# Sensorino.net
KiCad netlist of a schematic drawn in EAGLE
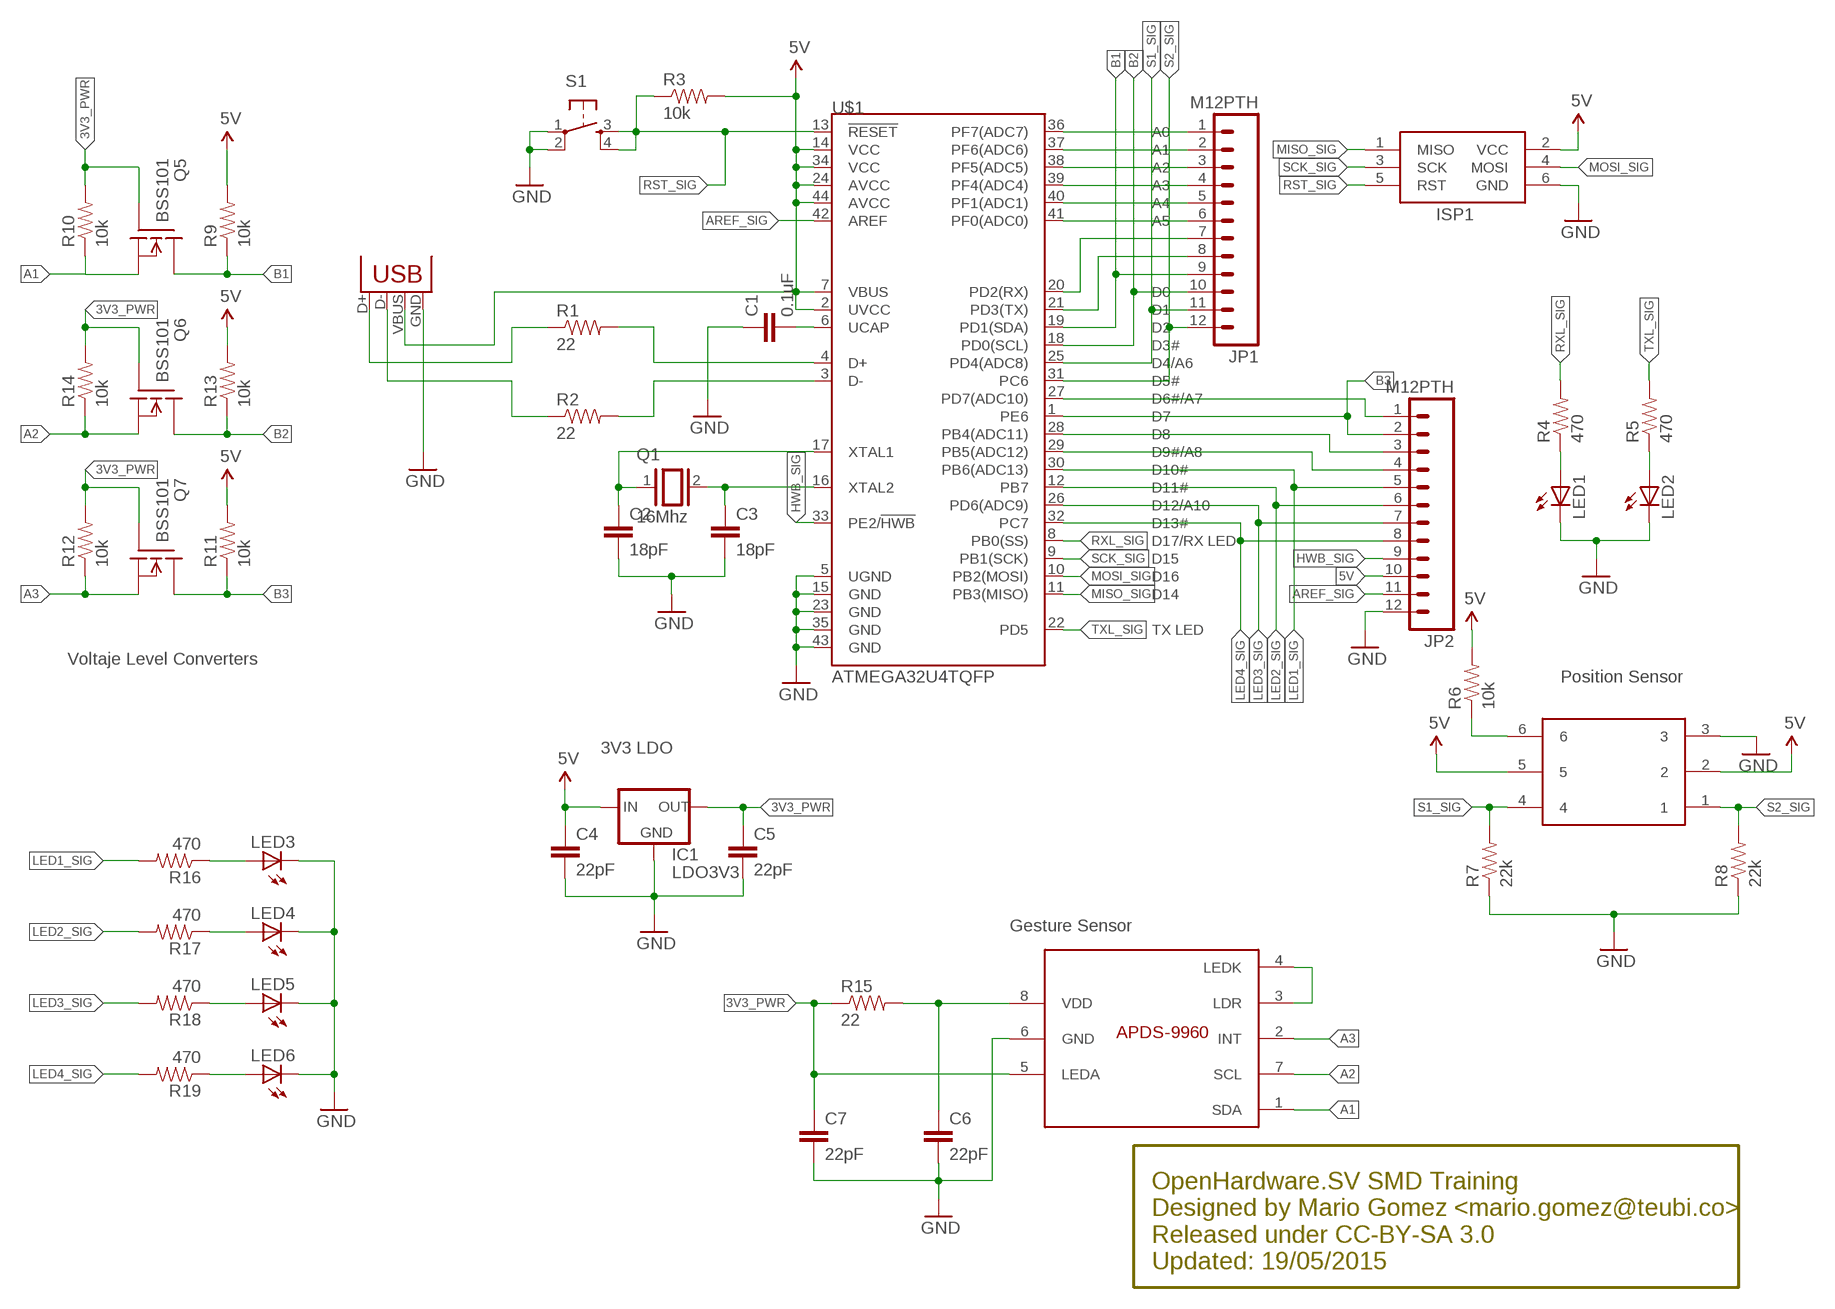
[diagram p0: schematic, sheet 1]

(export (version "E")
  (design (tool "Eeschema 10.0.6"))
  (components
    (comp (ref "C1")
      (value "0.1uF")
      (footprint "eagle-import:CAP-PTH-SMALL-KIT")
      (libsource (lib "eagle-import") (part "0.1UF-50V-20%(PTH)KIT-EZ"))
    )
    (comp (ref "C2")
      (value "18pF")
      (footprint "eagle-import:CAP-PTH-SMALL-KIT")
      (libsource (lib "eagle-import") (part "0.1UF-50V-20%(PTH)KIT-EZ"))
    )
    (comp (ref "C3")
      (value "18pF")
      (footprint "eagle-import:CAP-PTH-SMALL-KIT")
      (libsource (lib "eagle-import") (part "0.1UF-50V-20%(PTH)KIT-EZ"))
    )
    (comp (ref "C4")
      (value "22pF")
      (footprint "eagle-import:CAP-PTH-SMALL-KIT")
      (libsource (lib "eagle-import") (part "0.1UF-50V-20%(PTH)KIT-EZ"))
    )
    (comp (ref "C5")
      (value "22pF")
      (footprint "eagle-import:CAP-PTH-SMALL-KIT")
      (libsource (lib "eagle-import") (part "0.1UF-50V-20%(PTH)KIT-EZ"))
    )
    (comp (ref "C6")
      (value "22pF")
      (footprint "eagle-import:CAP-PTH-SMALL-KIT")
      (libsource (lib "eagle-import") (part "0.1UF-50V-20%(PTH)KIT-EZ"))
    )
    (comp (ref "C7")
      (value "22pF")
      (footprint "eagle-import:CAP-PTH-SMALL-KIT")
      (libsource (lib "eagle-import") (part "0.1UF-50V-20%(PTH)KIT-EZ"))
    )
    (comp (ref "IC1")
      (value "LDO3V3")
      (footprint "eagle-import:78XXL")
      (libsource (lib "eagle-import") (part "78XXL"))
    )
    (comp (ref "ISP1")
      (value "AVRISP-6")
      (footprint "eagle-import:AVRISP")
      (libsource (lib "eagle-import") (part "AVRISP-6"))
    )
    (comp (ref "JP1")
      (value "M12PTH")
      (footprint "eagle-import:1X12")
      (libsource (lib "eagle-import") (part "M12PTH"))
    )
    (comp (ref "JP2")
      (value "M12PTH")
      (footprint "eagle-import:1X12")
      (libsource (lib "eagle-import") (part "M12PTH"))
    )
    (comp (ref "LED1")
      (value "LED5MM")
      (footprint "eagle-import:LED5MM")
      (libsource (lib "eagle-import") (part "LED5MM"))
    )
    (comp (ref "LED2")
      (value "LED5MM")
      (footprint "eagle-import:LED5MM")
      (libsource (lib "eagle-import") (part "LED5MM"))
    )
    (comp (ref "LED3")
      (value "LED5MM")
      (footprint "eagle-import:LED5MM")
      (libsource (lib "eagle-import") (part "LED5MM"))
    )
    (comp (ref "LED4")
      (value "LED5MM")
      (footprint "eagle-import:LED5MM")
      (libsource (lib "eagle-import") (part "LED5MM"))
    )
    (comp (ref "LED5")
      (value "LED5MM")
      (footprint "eagle-import:LED5MM")
      (libsource (lib "eagle-import") (part "LED5MM"))
    )
    (comp (ref "LED6")
      (value "LED5MM")
      (footprint "eagle-import:LED5MM")
      (libsource (lib "eagle-import") (part "LED5MM"))
    )
    (comp (ref "Q1")
      (value "16Mhz")
      (footprint "eagle-import:QS")
      (libsource (lib "eagle-import") (part "XTAL/S"))
    )
    (comp (ref "Q5")
      (value "BSS101")
      (footprint "eagle-import:TO92")
      (libsource (lib "eagle-import") (part "BSS101"))
    )
    (comp (ref "Q6")
      (value "BSS101")
      (footprint "eagle-import:TO92")
      (libsource (lib "eagle-import") (part "BSS101"))
    )
    (comp (ref "Q7")
      (value "BSS101")
      (footprint "eagle-import:TO92")
      (libsource (lib "eagle-import") (part "BSS101"))
    )
    (comp (ref "R1")
      (value "22")
      (footprint "eagle-import:AXIAL-0.3")
      (libsource (lib "eagle-import") (part "RESISTORAXIAL-0.3"))
    )
    (comp (ref "R2")
      (value "22")
      (footprint "eagle-import:AXIAL-0.3")
      (libsource (lib "eagle-import") (part "RESISTORAXIAL-0.3"))
    )
    (comp (ref "R3")
      (value "10k")
      (footprint "eagle-import:AXIAL-0.3")
      (libsource (lib "eagle-import") (part "RESISTORAXIAL-0.3"))
    )
    (comp (ref "R4")
      (value "470")
      (footprint "eagle-import:AXIAL-0.3")
      (libsource (lib "eagle-import") (part "RESISTORAXIAL-0.3"))
    )
    (comp (ref "R5")
      (value "470")
      (footprint "eagle-import:AXIAL-0.3")
      (libsource (lib "eagle-import") (part "RESISTORAXIAL-0.3"))
    )
    (comp (ref "R6")
      (value "10k")
      (footprint "eagle-import:AXIAL-0.3")
      (libsource (lib "eagle-import") (part "RESISTORAXIAL-0.3"))
    )
    (comp (ref "R7")
      (value "22k")
      (footprint "eagle-import:AXIAL-0.3")
      (libsource (lib "eagle-import") (part "RESISTORAXIAL-0.3"))
    )
    (comp (ref "R8")
      (value "22k")
      (footprint "eagle-import:AXIAL-0.3")
      (libsource (lib "eagle-import") (part "RESISTORAXIAL-0.3"))
    )
    (comp (ref "R9")
      (value "10k")
      (footprint "eagle-import:AXIAL-0.3")
      (libsource (lib "eagle-import") (part "RESISTORAXIAL-0.3"))
    )
    (comp (ref "R10")
      (value "10k")
      (footprint "eagle-import:AXIAL-0.3")
      (libsource (lib "eagle-import") (part "RESISTORAXIAL-0.3"))
    )
    (comp (ref "R11")
      (value "10k")
      (footprint "eagle-import:AXIAL-0.3")
      (libsource (lib "eagle-import") (part "RESISTORAXIAL-0.3"))
    )
    (comp (ref "R12")
      (value "10k")
      (footprint "eagle-import:AXIAL-0.3")
      (libsource (lib "eagle-import") (part "RESISTORAXIAL-0.3"))
    )
    (comp (ref "R13")
      (value "10k")
      (footprint "eagle-import:AXIAL-0.3")
      (libsource (lib "eagle-import") (part "RESISTORAXIAL-0.3"))
    )
    (comp (ref "R14")
      (value "10k")
      (footprint "eagle-import:AXIAL-0.3")
      (libsource (lib "eagle-import") (part "RESISTORAXIAL-0.3"))
    )
    (comp (ref "R15")
      (value "22")
      (footprint "eagle-import:AXIAL-0.3")
      (libsource (lib "eagle-import") (part "RESISTORAXIAL-0.3"))
    )
    (comp (ref "R16")
      (value "470")
      (footprint "eagle-import:AXIAL-0.3")
      (libsource (lib "eagle-import") (part "RESISTORAXIAL-0.3"))
    )
    (comp (ref "R17")
      (value "470")
      (footprint "eagle-import:AXIAL-0.3")
      (libsource (lib "eagle-import") (part "RESISTORAXIAL-0.3"))
    )
    (comp (ref "R18")
      (value "470")
      (footprint "eagle-import:AXIAL-0.3")
      (libsource (lib "eagle-import") (part "RESISTORAXIAL-0.3"))
    )
    (comp (ref "R19")
      (value "470")
      (footprint "eagle-import:AXIAL-0.3")
      (libsource (lib "eagle-import") (part "RESISTORAXIAL-0.3"))
    )
    (comp (ref "S1")
      (value "TAC_SWITCHPTH")
      (footprint "eagle-import:TACTILE-PTH")
      (libsource (lib "eagle-import") (part "TAC_SWITCHPTH"))
    )
    (comp (ref "U$1")
      (value "ATMEGA32U4TQFP")
      (footprint "eagle-import:SPARKFUN-DIGITALIC_TQFP44")
      (libsource (lib "eagle-import") (part "ATMEGA32U4TQFP"))
    )
    (comp (ref "U$2")
      (value "USBPTH")
      (footprint "eagle-import:USB-B-PTH")
      (libsource (lib "eagle-import") (part "USBPTH"))
    )
    (comp (ref "U$3")
      (value "RPI-1031")
      (footprint "eagle-import:RPI-1031")
      (libsource (lib "eagle-import") (part "RPI-1031"))
    )
    (comp (ref "U$4")
      (value "APDS-9960")
      (footprint "eagle-import:APDS-9960")
      (libsource (lib "eagle-import") (part "APDS-9960"))
    )
  )
  (nets
    (net (code "1") (name "3V3_PWR") (class "Default")
      (node (ref "C5") (pin "1") (pinfunction "1_1") (pintype "passive"))
      (node (ref "C7") (pin "1") (pinfunction "1_1") (pintype "passive"))
      (node (ref "IC1") (pin "OUT") (pinfunction "OUT_OUT") (pintype "passive"))
      (node (ref "Q5") (pin "2") (pinfunction "G_2") (pintype "passive"))
      (node (ref "Q6") (pin "2") (pinfunction "G_2") (pintype "passive"))
      (node (ref "Q7") (pin "2") (pinfunction "G_2") (pintype "passive"))
      (node (ref "R10") (pin "P$2") (pinfunction "2_P$2") (pintype "passive"))
      (node (ref "R12") (pin "P$2") (pinfunction "2_P$2") (pintype "passive"))
      (node (ref "R14") (pin "P$2") (pinfunction "2_P$2") (pintype "passive"))
      (node (ref "R15") (pin "P$1") (pinfunction "1_P$1") (pintype "passive"))
      (node (ref "U$4") (pin "5") (pinfunction "LEDA_5") (pintype "bidirectional"))
    )
    (net (code "2") (name "5V") (class "Default")
      (node (ref "C4") (pin "1") (pinfunction "1_1") (pintype "passive"))
      (node (ref "IC1") (pin "IN") (pinfunction "IN_IN") (pintype "input"))
      (node (ref "ISP1") (pin "2") (pinfunction "VCC_2") (pintype "power_in"))
      (node (ref "JP2") (pin "10") (pinfunction "10_10") (pintype "passive"))
      (node (ref "R11") (pin "P$2") (pinfunction "2_P$2") (pintype "passive"))
      (node (ref "R13") (pin "P$2") (pinfunction "2_P$2") (pintype "passive"))
      (node (ref "R3") (pin "P$2") (pinfunction "2_P$2") (pintype "passive"))
      (node (ref "R6") (pin "P$2") (pinfunction "2_P$2") (pintype "passive"))
      (node (ref "R9") (pin "P$2") (pinfunction "2_P$2") (pintype "passive"))
      (node (ref "U$1") (pin "14") (pinfunction "VCC_14") (pintype "bidirectional"))
      (node (ref "U$1") (pin "2") (pinfunction "UVCC_2") (pintype "bidirectional"))
      (node (ref "U$1") (pin "24") (pinfunction "AVCC_24") (pintype "bidirectional"))
      (node (ref "U$1") (pin "34") (pinfunction "VCC_34") (pintype "bidirectional"))
      (node (ref "U$1") (pin "44") (pinfunction "AVCC_44") (pintype "bidirectional"))
      (node (ref "U$1") (pin "7") (pinfunction "VBUS_7") (pintype "bidirectional"))
      (node (ref "U$2") (pin "VBUS") (pinfunction "VBUS_VBUS") (pintype "bidirectional"))
      (node (ref "U$3") (pin "2") (pinfunction "2_2") (pintype "bidirectional"))
      (node (ref "U$3") (pin "5") (pinfunction "5_5") (pintype "bidirectional"))
    )
    (net (code "3") (name "A1") (class "Default")
      (node (ref "Q5") (pin "1") (pinfunction "S_1") (pintype "passive"))
      (node (ref "R10") (pin "P$1") (pinfunction "1_P$1") (pintype "passive"))
      (node (ref "U$4") (pin "1") (pinfunction "SDA_1") (pintype "bidirectional"))
    )
    (net (code "4") (name "A2") (class "Default")
      (node (ref "Q6") (pin "1") (pinfunction "S_1") (pintype "passive"))
      (node (ref "R14") (pin "P$1") (pinfunction "1_P$1") (pintype "passive"))
      (node (ref "U$4") (pin "7") (pinfunction "SCL_7") (pintype "bidirectional"))
    )
    (net (code "5") (name "A3") (class "Default")
      (node (ref "Q7") (pin "1") (pinfunction "S_1") (pintype "passive"))
      (node (ref "R12") (pin "P$1") (pinfunction "1_P$1") (pintype "passive"))
      (node (ref "U$4") (pin "2") (pinfunction "INT_2") (pintype "bidirectional"))
    )
    (net (code "6") (name "AREF_SIG") (class "Default")
      (node (ref "JP2") (pin "11") (pinfunction "11_11") (pintype "passive"))
      (node (ref "U$1") (pin "42") (pinfunction "AREF_42") (pintype "bidirectional"))
    )
    (net (code "7") (name "B1") (class "Default")
      (node (ref "JP1") (pin "9") (pinfunction "9_9") (pintype "passive"))
      (node (ref "Q5") (pin "3") (pinfunction "D_3") (pintype "passive"))
      (node (ref "R9") (pin "P$1") (pinfunction "1_P$1") (pintype "passive"))
      (node (ref "U$1") (pin "19") (pinfunction "PD1(SDA)_19") (pintype "bidirectional"))
    )
    (net (code "8") (name "B2") (class "Default")
      (node (ref "JP1") (pin "10") (pinfunction "10_10") (pintype "passive"))
      (node (ref "Q6") (pin "3") (pinfunction "D_3") (pintype "passive"))
      (node (ref "R13") (pin "P$1") (pinfunction "1_P$1") (pintype "passive"))
      (node (ref "U$1") (pin "18") (pinfunction "PD0(SCL)_18") (pintype "bidirectional"))
    )
    (net (code "9") (name "B3") (class "Default")
      (node (ref "JP2") (pin "2") (pinfunction "2_2") (pintype "passive"))
      (node (ref "Q7") (pin "3") (pinfunction "D_3") (pintype "passive"))
      (node (ref "R11") (pin "P$1") (pinfunction "1_P$1") (pintype "passive"))
      (node (ref "U$1") (pin "1") (pinfunction "PE6_1") (pintype "bidirectional"))
    )
    (net (code "10") (name "GND") (class "Default")
      (node (ref "C1") (pin "1") (pinfunction "1_1") (pintype "passive"))
      (node (ref "C2") (pin "2") (pinfunction "2_2") (pintype "passive"))
      (node (ref "C3") (pin "2") (pinfunction "2_2") (pintype "passive"))
      (node (ref "C4") (pin "2") (pinfunction "2_2") (pintype "passive"))
      (node (ref "C5") (pin "2") (pinfunction "2_2") (pintype "passive"))
      (node (ref "C6") (pin "2") (pinfunction "2_2") (pintype "passive"))
      (node (ref "C7") (pin "2") (pinfunction "2_2") (pintype "passive"))
      (node (ref "IC1") (pin "GND") (pinfunction "GND_GND") (pintype "input"))
      (node (ref "ISP1") (pin "6") (pinfunction "GND_6") (pintype "power_in"))
      (node (ref "JP2") (pin "12") (pinfunction "12_12") (pintype "passive"))
      (node (ref "LED1") (pin "K") (pinfunction "C_K") (pintype "passive"))
      (node (ref "LED2") (pin "K") (pinfunction "C_K") (pintype "passive"))
      (node (ref "LED3") (pin "K") (pinfunction "C_K") (pintype "passive"))
      (node (ref "LED4") (pin "K") (pinfunction "C_K") (pintype "passive"))
      (node (ref "LED5") (pin "K") (pinfunction "C_K") (pintype "passive"))
      (node (ref "LED6") (pin "K") (pinfunction "C_K") (pintype "passive"))
      (node (ref "R7") (pin "P$1") (pinfunction "1_P$1") (pintype "passive"))
      (node (ref "R8") (pin "P$1") (pinfunction "1_P$1") (pintype "passive"))
      (node (ref "S1") (pin "1") (pinfunction "1_1") (pintype "passive"))
      (node (ref "S1") (pin "2") (pinfunction "2_2") (pintype "passive"))
      (node (ref "U$1") (pin "15") (pinfunction "GND_15") (pintype "bidirectional"))
      (node (ref "U$1") (pin "23") (pinfunction "GND_23") (pintype "bidirectional"))
      (node (ref "U$1") (pin "35") (pinfunction "GND_35") (pintype "bidirectional"))
      (node (ref "U$1") (pin "43") (pinfunction "GND_43") (pintype "bidirectional"))
      (node (ref "U$1") (pin "5") (pinfunction "UGND_5") (pintype "bidirectional"))
      (node (ref "U$2") (pin "GND") (pinfunction "GND_GND") (pintype "bidirectional"))
      (node (ref "U$3") (pin "3") (pinfunction "3_3") (pintype "bidirectional"))
      (node (ref "U$4") (pin "6") (pinfunction "GND_6") (pintype "bidirectional"))
    )
    (net (code "11") (name "HWB_SIG") (class "Default")
      (node (ref "JP2") (pin "9") (pinfunction "9_9") (pintype "passive"))
      (node (ref "U$1") (pin "33") (pinfunction "PE2/~{HWB}_33") (pintype "bidirectional"))
    )
    (net (code "12") (name "LED1_SIG") (class "Default")
      (node (ref "JP2") (pin "5") (pinfunction "5_5") (pintype "passive"))
      (node (ref "R16") (pin "P$2") (pinfunction "2_P$2") (pintype "passive"))
      (node (ref "U$1") (pin "30") (pinfunction "PB6(ADC13)_30") (pintype "bidirectional"))
    )
    (net (code "13") (name "LED2_SIG") (class "Default")
      (node (ref "JP2") (pin "6") (pinfunction "6_6") (pintype "passive"))
      (node (ref "R17") (pin "P$2") (pinfunction "2_P$2") (pintype "passive"))
      (node (ref "U$1") (pin "12") (pinfunction "PB7_12") (pintype "bidirectional"))
    )
    (net (code "14") (name "LED3_SIG") (class "Default")
      (node (ref "JP2") (pin "7") (pinfunction "7_7") (pintype "passive"))
      (node (ref "R18") (pin "P$2") (pinfunction "2_P$2") (pintype "passive"))
      (node (ref "U$1") (pin "26") (pinfunction "PD6(ADC9)_26") (pintype "bidirectional"))
    )
    (net (code "15") (name "LED4_SIG") (class "Default")
      (node (ref "JP2") (pin "8") (pinfunction "8_8") (pintype "passive"))
      (node (ref "R19") (pin "P$2") (pinfunction "2_P$2") (pintype "passive"))
      (node (ref "U$1") (pin "32") (pinfunction "PC7_32") (pintype "bidirectional"))
    )
    (net (code "16") (name "MISO_SIG") (class "Default")
      (node (ref "ISP1") (pin "1") (pinfunction "MISO_1") (pintype "input"))
      (node (ref "U$1") (pin "11") (pinfunction "PB3(MISO)_11") (pintype "bidirectional"))
    )
    (net (code "17") (name "MOSI_SIG") (class "Default")
      (node (ref "ISP1") (pin "4") (pinfunction "MOSI_4") (pintype "output"))
      (node (ref "U$1") (pin "10") (pinfunction "PB2(MOSI)_10") (pintype "bidirectional"))
    )
    (net (code "18") (name "Net-(R1-1)") (class "Default")
      (node (ref "R1") (pin "P$1") (pinfunction "1_P$1") (pintype "passive"))
      (node (ref "U$2") (pin "D+") (pinfunction "D+_D+") (pintype "bidirectional"))
    )
    (net (code "19") (name "Net-(R1-2)") (class "Default")
      (node (ref "R1") (pin "P$2") (pinfunction "2_P$2") (pintype "passive"))
      (node (ref "U$1") (pin "4") (pinfunction "D+_4") (pintype "bidirectional"))
    )
    (net (code "20") (name "Net-(R2-1)") (class "Default")
      (node (ref "R2") (pin "P$1") (pinfunction "1_P$1") (pintype "passive"))
      (node (ref "U$2") (pin "D-") (pinfunction "D-_D-") (pintype "bidirectional"))
    )
    (net (code "21") (name "Net-(R2-2)") (class "Default")
      (node (ref "R2") (pin "P$2") (pinfunction "2_P$2") (pintype "passive"))
      (node (ref "U$1") (pin "3") (pinfunction "D-_3") (pintype "bidirectional"))
    )
    (net (code "22") (name "Net-(R4-1)") (class "Default")
      (node (ref "LED1") (pin "A") (pinfunction "A_A") (pintype "passive"))
      (node (ref "R4") (pin "P$1") (pinfunction "1_P$1") (pintype "passive"))
    )
    (net (code "23") (name "Net-(R5-1)") (class "Default")
      (node (ref "LED2") (pin "A") (pinfunction "A_A") (pintype "passive"))
      (node (ref "R5") (pin "P$1") (pinfunction "1_P$1") (pintype "passive"))
    )
    (net (code "24") (name "Net-(R6-1)") (class "Default")
      (node (ref "R6") (pin "P$1") (pinfunction "1_P$1") (pintype "passive"))
      (node (ref "U$3") (pin "6") (pinfunction "6_6") (pintype "bidirectional"))
    )
    (net (code "25") (name "Net-(R15-2)") (class "Default")
      (node (ref "C6") (pin "1") (pinfunction "1_1") (pintype "passive"))
      (node (ref "R15") (pin "P$2") (pinfunction "2_P$2") (pintype "passive"))
      (node (ref "U$4") (pin "8") (pinfunction "VDD_8") (pintype "bidirectional"))
    )
    (net (code "26") (name "Net-(R16-1)") (class "Default")
      (node (ref "LED3") (pin "A") (pinfunction "A_A") (pintype "passive"))
      (node (ref "R16") (pin "P$1") (pinfunction "1_P$1") (pintype "passive"))
    )
    (net (code "27") (name "Net-(R17-1)") (class "Default")
      (node (ref "LED4") (pin "A") (pinfunction "A_A") (pintype "passive"))
      (node (ref "R17") (pin "P$1") (pinfunction "1_P$1") (pintype "passive"))
    )
    (net (code "28") (name "Net-(R18-1)") (class "Default")
      (node (ref "LED5") (pin "A") (pinfunction "A_A") (pintype "passive"))
      (node (ref "R18") (pin "P$1") (pinfunction "1_P$1") (pintype "passive"))
    )
    (net (code "29") (name "Net-(R19-1)") (class "Default")
      (node (ref "LED6") (pin "A") (pinfunction "A_A") (pintype "passive"))
      (node (ref "R19") (pin "P$1") (pinfunction "1_P$1") (pintype "passive"))
    )
    (net (code "30") (name "Net-(U$1-PB4(ADC11))") (class "Default")
      (node (ref "JP2") (pin "3") (pinfunction "3_3") (pintype "passive"))
      (node (ref "U$1") (pin "28") (pinfunction "PB4(ADC11)_28") (pintype "bidirectional"))
    )
    (net (code "31") (name "Net-(U$1-PB5(ADC12))") (class "Default")
      (node (ref "JP2") (pin "4") (pinfunction "4_4") (pintype "passive"))
      (node (ref "U$1") (pin "29") (pinfunction "PB5(ADC12)_29") (pintype "bidirectional"))
    )
    (net (code "32") (name "Net-(U$1-PD2(RX))") (class "Default")
      (node (ref "JP1") (pin "7") (pinfunction "7_7") (pintype "passive"))
      (node (ref "U$1") (pin "20") (pinfunction "PD2(RX)_20") (pintype "bidirectional"))
    )
    (net (code "33") (name "Net-(U$1-PD3(TX))") (class "Default")
      (node (ref "JP1") (pin "8") (pinfunction "8_8") (pintype "passive"))
      (node (ref "U$1") (pin "21") (pinfunction "PD3(TX)_21") (pintype "bidirectional"))
    )
    (net (code "34") (name "Net-(U$1-PD7(ADC10))") (class "Default")
      (node (ref "JP2") (pin "1") (pinfunction "1_1") (pintype "passive"))
      (node (ref "U$1") (pin "27") (pinfunction "PD7(ADC10)_27") (pintype "bidirectional"))
    )
    (net (code "35") (name "Net-(U$1-PF0(ADC0))") (class "Default")
      (node (ref "JP1") (pin "6") (pinfunction "6_6") (pintype "passive"))
      (node (ref "U$1") (pin "41") (pinfunction "PF0(ADC0)_41") (pintype "bidirectional"))
    )
    (net (code "36") (name "Net-(U$1-PF1(ADC1))") (class "Default")
      (node (ref "JP1") (pin "5") (pinfunction "5_5") (pintype "passive"))
      (node (ref "U$1") (pin "40") (pinfunction "PF1(ADC1)_40") (pintype "bidirectional"))
    )
    (net (code "37") (name "Net-(U$1-PF4(ADC4))") (class "Default")
      (node (ref "JP1") (pin "4") (pinfunction "4_4") (pintype "passive"))
      (node (ref "U$1") (pin "39") (pinfunction "PF4(ADC4)_39") (pintype "bidirectional"))
    )
    (net (code "38") (name "Net-(U$1-PF5(ADC5))") (class "Default")
      (node (ref "JP1") (pin "3") (pinfunction "3_3") (pintype "passive"))
      (node (ref "U$1") (pin "38") (pinfunction "PF5(ADC5)_38") (pintype "bidirectional"))
    )
    (net (code "39") (name "Net-(U$1-PF6(ADC6))") (class "Default")
      (node (ref "JP1") (pin "2") (pinfunction "2_2") (pintype "passive"))
      (node (ref "U$1") (pin "37") (pinfunction "PF6(ADC6)_37") (pintype "bidirectional"))
    )
    (net (code "40") (name "Net-(U$1-PF7(ADC7))") (class "Default")
      (node (ref "JP1") (pin "1") (pinfunction "1_1") (pintype "passive"))
      (node (ref "U$1") (pin "36") (pinfunction "PF7(ADC7)_36") (pintype "bidirectional"))
    )
    (net (code "41") (name "Net-(U$1-UCAP)") (class "Default")
      (node (ref "C1") (pin "2") (pinfunction "2_2") (pintype "passive"))
      (node (ref "U$1") (pin "6") (pinfunction "UCAP_6") (pintype "bidirectional"))
    )
    (net (code "42") (name "Net-(U$1-XTAL1)") (class "Default")
      (node (ref "C2") (pin "1") (pinfunction "1_1") (pintype "passive"))
      (node (ref "Q1") (pin "1") (pinfunction "1_1") (pintype "passive"))
      (node (ref "U$1") (pin "17") (pinfunction "XTAL1_17") (pintype "bidirectional"))
    )
    (net (code "43") (name "Net-(U$1-XTAL2)") (class "Default")
      (node (ref "C3") (pin "1") (pinfunction "1_1") (pintype "passive"))
      (node (ref "Q1") (pin "2") (pinfunction "2_2") (pintype "passive"))
      (node (ref "U$1") (pin "16") (pinfunction "XTAL2_16") (pintype "bidirectional"))
    )
    (net (code "44") (name "Net-(U$4-LDR)") (class "Default")
      (node (ref "U$4") (pin "3") (pinfunction "LDR_3") (pintype "bidirectional"))
      (node (ref "U$4") (pin "4") (pinfunction "LEDK_4") (pintype "bidirectional"))
    )
    (net (code "45") (name "RST_SIG") (class "Default")
      (node (ref "ISP1") (pin "5") (pinfunction "RST_5") (pintype "output"))
      (node (ref "R3") (pin "P$1") (pinfunction "1_P$1") (pintype "passive"))
      (node (ref "S1") (pin "3") (pinfunction "3_3") (pintype "passive"))
      (node (ref "S1") (pin "4") (pinfunction "4_4") (pintype "passive"))
      (node (ref "U$1") (pin "13") (pinfunction "~{RESET}_13") (pintype "bidirectional"))
    )
    (net (code "46") (name "RXL_SIG") (class "Default")
      (node (ref "R4") (pin "P$2") (pinfunction "2_P$2") (pintype "passive"))
      (node (ref "U$1") (pin "8") (pinfunction "PB0(SS)_8") (pintype "bidirectional"))
    )
    (net (code "47") (name "S1_SIG") (class "Default")
      (node (ref "JP1") (pin "11") (pinfunction "11_11") (pintype "passive"))
      (node (ref "R7") (pin "P$2") (pinfunction "2_P$2") (pintype "passive"))
      (node (ref "U$1") (pin "25") (pinfunction "PD4(ADC8)_25") (pintype "bidirectional"))
      (node (ref "U$3") (pin "4") (pinfunction "4_4") (pintype "bidirectional"))
    )
    (net (code "48") (name "S2_SIG") (class "Default")
      (node (ref "JP1") (pin "12") (pinfunction "12_12") (pintype "passive"))
      (node (ref "R8") (pin "P$2") (pinfunction "2_P$2") (pintype "passive"))
      (node (ref "U$1") (pin "31") (pinfunction "PC6_31") (pintype "bidirectional"))
      (node (ref "U$3") (pin "1") (pinfunction "1_1") (pintype "bidirectional"))
    )
    (net (code "49") (name "SCK_SIG") (class "Default")
      (node (ref "ISP1") (pin "3") (pinfunction "SCK_3") (pintype "output"))
      (node (ref "U$1") (pin "9") (pinfunction "PB1(SCK)_9") (pintype "bidirectional"))
    )
    (net (code "50") (name "TXL_SIG") (class "Default")
      (node (ref "R5") (pin "P$2") (pinfunction "2_P$2") (pintype "passive"))
      (node (ref "U$1") (pin "22") (pinfunction "PD5_22") (pintype "bidirectional"))
    )
  )
)
